# AQE_SENSORMODULE_E2V_CMOS.net
KiCad netlist of a schematic drawn in EAGLE
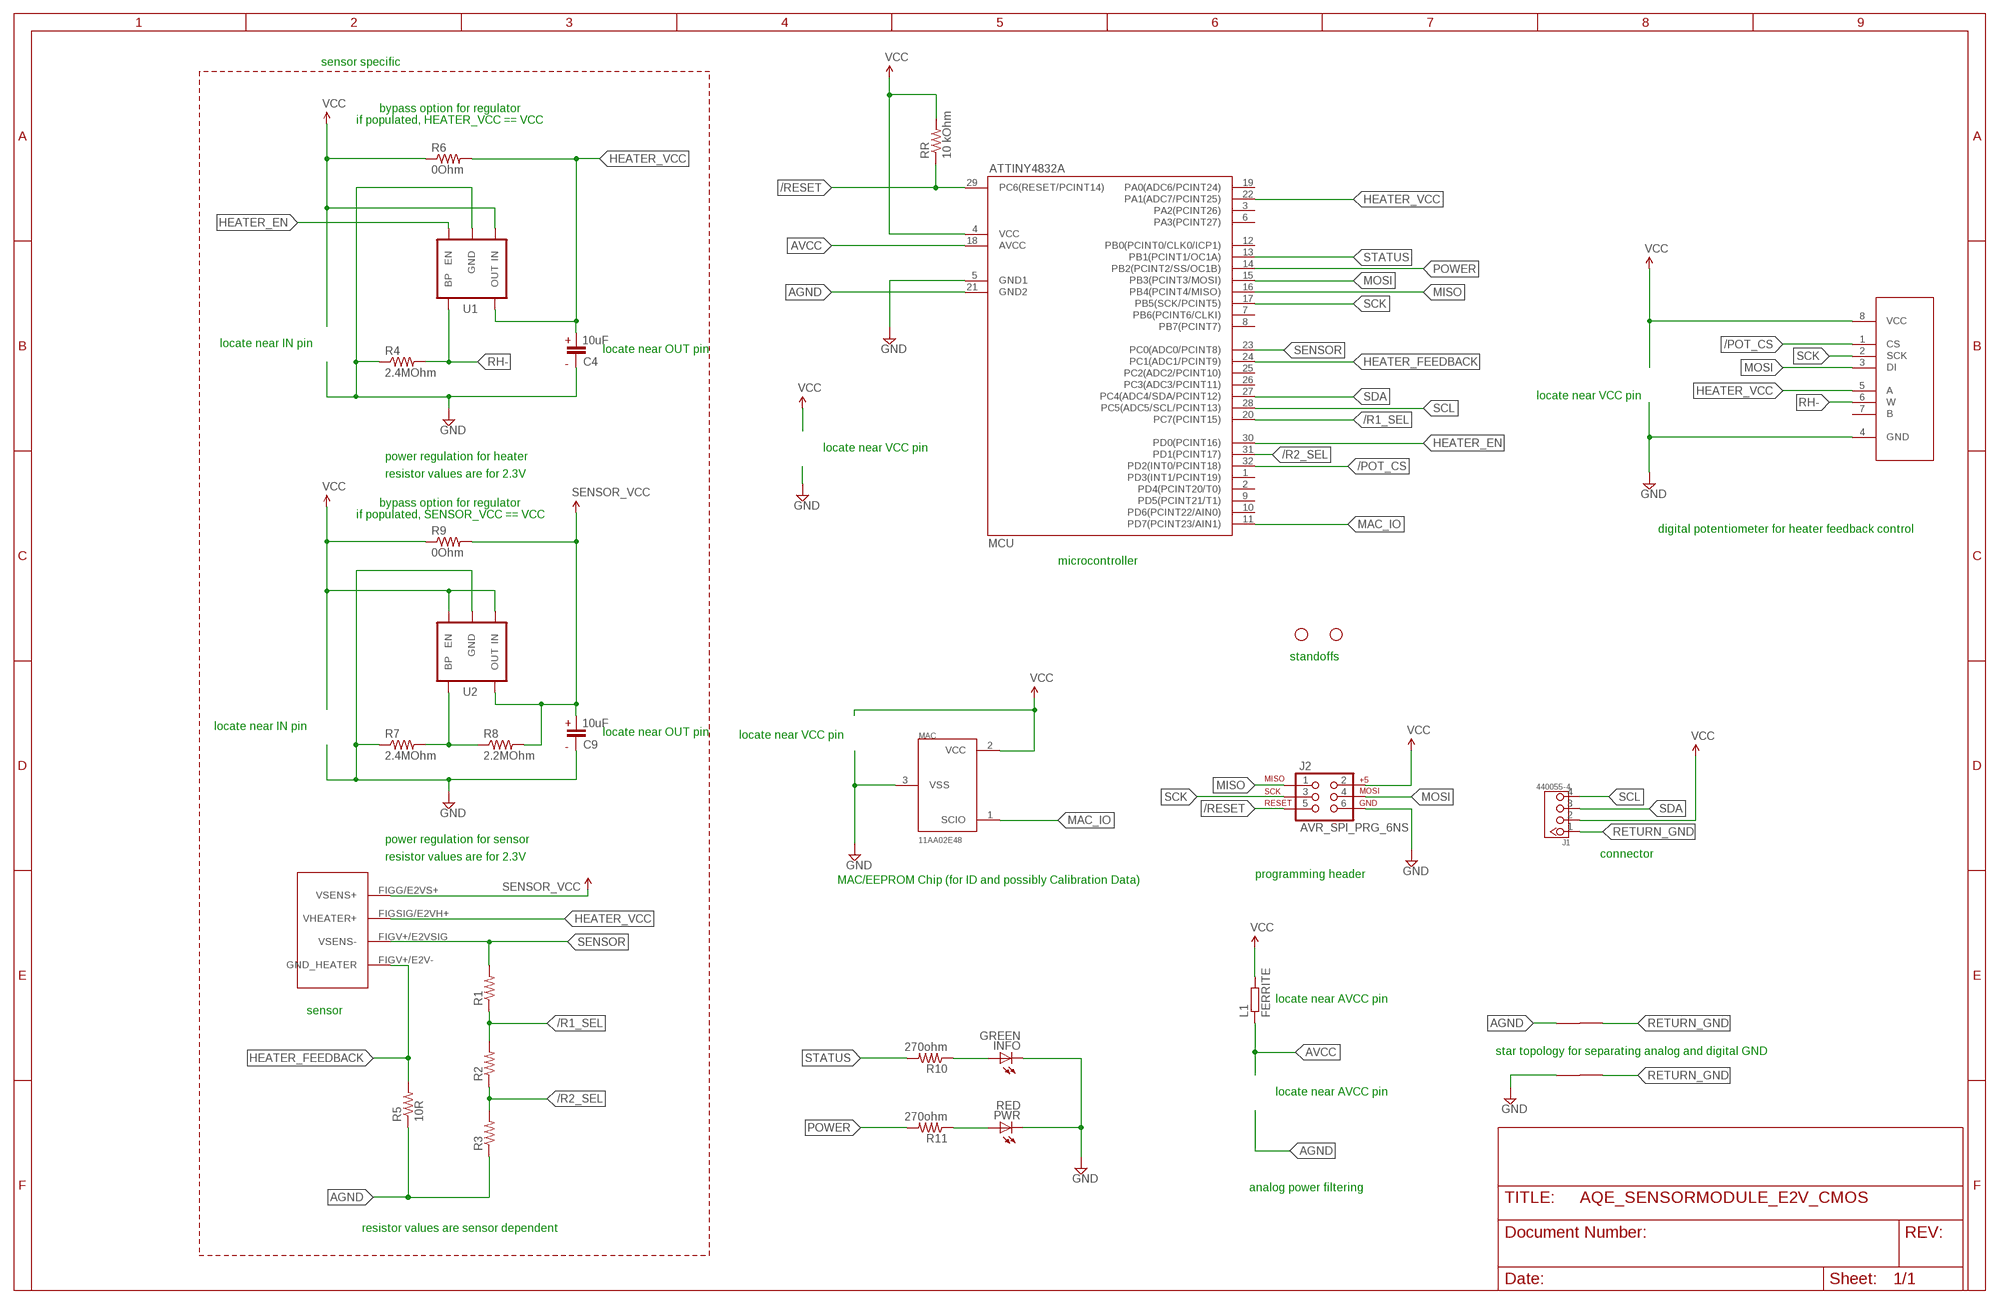
[diagram p0: schematic, sheet 1]

(export (version "E")
  (design (tool "Eeschema 10.0.6"))
  (components
    (comp (ref "C4")
      (value "10uF")
      (footprint "eagle-import:TYPE-B_ALUMINUM_CAN")
      (libsource (lib "eagle-import") (part "EEE-1EA100WR"))
    )
    (comp (ref "C9")
      (value "10uF")
      (footprint "eagle-import:TYPE-B_ALUMINUM_CAN")
      (libsource (lib "eagle-import") (part "EEE-1EA100WR"))
    )
    (comp (ref "GAS")
      (value "E2V")
      (footprint "eagle-import:SR-4")
      (libsource (lib "eagle-import") (part "E2V"))
    )
    (comp (ref "INFO")
      (value "GREEN")
      (footprint "eagle-import:CHIPLED_0805")
      (libsource (lib "eagle-import") (part "LEDCHIPLED_0805"))
    )
    (comp (ref "J1")
      (value "440055-4")
      (footprint "eagle-import:2.0_1X4_90")
      (libsource (lib "eagle-import") (part "TWIG_2.0-DIP-FEMALED"))
    )
    (comp (ref "J2")
      (value "AVR_SPI_PRG_6NS")
      (footprint "eagle-import:2X3-NS")
      (libsource (lib "eagle-import") (part "AVR_SPI_PRG_6NS"))
    )
    (comp (ref "JP1")
      (value "STAND-OFF")
      (footprint "eagle-import:STAND-OFF")
      (libsource (lib "eagle-import") (part "STAND-OFF"))
    )
    (comp (ref "JP2")
      (value "STAND-OFF")
      (footprint "eagle-import:STAND-OFF")
      (libsource (lib "eagle-import") (part "STAND-OFF"))
    )
    (comp (ref "L1")
      (value "FERRITE")
      (footprint "eagle-import:RCL_R0805")
      (libsource (lib "eagle-import") (part "RCL_R-EU_R0805"))
    )
    (comp (ref "MAC")
      (value "11AA02E48")
      (footprint "eagle-import:SOT23")
      (libsource (lib "eagle-import") (part "11AA02E48"))
    )
    (comp (ref "MCU")
      (value "ATTINY4832A")
      (footprint "eagle-import:TQFP32-08")
      (libsource (lib "eagle-import") (part "ATTINY4832A"))
    )
    (comp (ref "PWR")
      (value "RED")
      (footprint "eagle-import:CHIPLED_0805")
      (libsource (lib "eagle-import") (part "LEDCHIPLED_0805"))
    )
    (comp (ref "R1")
      (value "RESISTOR0805-RES")
      (footprint "eagle-import:0805")
      (libsource (lib "eagle-import") (part "RESISTOR0805-RES"))
    )
    (comp (ref "R2")
      (value "RESISTOR0805-RES")
      (footprint "eagle-import:0805")
      (libsource (lib "eagle-import") (part "RESISTOR0805-RES"))
    )
    (comp (ref "R3")
      (value "RESISTOR0805-RES")
      (footprint "eagle-import:0805")
      (libsource (lib "eagle-import") (part "RESISTOR0805-RES"))
    )
    (comp (ref "R4")
      (value "2.4MOhm")
      (footprint "eagle-import:0805")
      (libsource (lib "eagle-import") (part "RESISTOR0805-RES"))
    )
    (comp (ref "R5")
      (value "10R")
      (footprint "eagle-import:0805")
      (libsource (lib "eagle-import") (part "RESISTOR0805-RES"))
    )
    (comp (ref "R6")
      (value "0Ohm")
      (footprint "eagle-import:0805")
      (libsource (lib "eagle-import") (part "RESISTOR0805-RES"))
    )
    (comp (ref "R7")
      (value "2.4MOhm")
      (footprint "eagle-import:0805")
      (libsource (lib "eagle-import") (part "RESISTOR0805-RES"))
    )
    (comp (ref "R8")
      (value "2.2MOhm")
      (footprint "eagle-import:0805")
      (libsource (lib "eagle-import") (part "RESISTOR0805-RES"))
    )
    (comp (ref "R9")
      (value "0Ohm")
      (footprint "eagle-import:0805")
      (libsource (lib "eagle-import") (part "RESISTOR0805-RES"))
    )
    (comp (ref "R10")
      (value "270ohm")
      (footprint "eagle-import:0805")
      (libsource (lib "eagle-import") (part "RESISTOR0805-RES"))
    )
    (comp (ref "R11")
      (value "270ohm")
      (footprint "eagle-import:0805")
      (libsource (lib "eagle-import") (part "RESISTOR0805-RES"))
    )
    (comp (ref "RR")
      (value "10 kOhm")
      (footprint "eagle-import:0805")
      (libsource (lib "eagle-import") (part "RESISTOR0805-RES"))
    )
    (comp (ref "U$2")
      (value "PLANE_COUPLER")
      (footprint "eagle-import:PLANE_COUPLER")
      (libsource (lib "eagle-import") (part "PLANE_COUPLER"))
    )
    (comp (ref "U$3")
      (value "PLANE_COUPLER")
      (footprint "eagle-import:PLANE_COUPLER")
      (libsource (lib "eagle-import") (part "PLANE_COUPLER"))
    )
    (comp (ref "U1")
      (value "V_REG_LDOSMD")
      (footprint "eagle-import:SOT23-5")
      (libsource (lib "eagle-import") (part "V_REG_LDOSMD"))
    )
    (comp (ref "U2")
      (value "V_REG_LDOSMD")
      (footprint "eagle-import:SOT23-5")
      (libsource (lib "eagle-import") (part "V_REG_LDOSMD"))
    )
    (comp (ref "U3")
      (value "MCP41XXX")
      (footprint "eagle-import:SO08")
      (libsource (lib "eagle-import") (part "MCP41XXX"))
    )
  )
  (nets
    (net (code "1") (name "AGND") (class "Default")
      (node (ref "MCU") (pin "21") (pinfunction "GND2_21") (pintype "power_in"))
      (node (ref "R3") (pin "1") (pinfunction "1_1") (pintype "passive"))
      (node (ref "R5") (pin "1") (pinfunction "1_1") (pintype "passive"))
      (node (ref "U$2") (pin "1") (pinfunction "P$1_1") (pintype "bidirectional"))
    )
    (net (code "2") (name "AVCC") (class "Default")
      (node (ref "L1") (pin "1") (pinfunction "1_1") (pintype "passive"))
      (node (ref "MCU") (pin "18") (pinfunction "AVCC_18") (pintype "power_in"))
    )
    (net (code "3") (name "GND") (class "Default")
      (node (ref "C4") (pin "P$2") (pinfunction "2_P$2") (pintype "passive"))
      (node (ref "C9") (pin "P$2") (pinfunction "2_P$2") (pintype "passive"))
      (node (ref "INFO") (pin "C") (pinfunction "C_C") (pintype "passive"))
      (node (ref "J2") (pin "6") (pinfunction "6_6") (pintype "passive"))
      (node (ref "MAC") (pin "3") (pinfunction "VSS_3") (pintype "bidirectional"))
      (node (ref "MCU") (pin "5") (pinfunction "GND1_5") (pintype "power_in"))
      (node (ref "PWR") (pin "C") (pinfunction "C_C") (pintype "passive"))
      (node (ref "R4") (pin "1") (pinfunction "1_1") (pintype "passive"))
      (node (ref "R7") (pin "1") (pinfunction "1_1") (pintype "passive"))
      (node (ref "U$3") (pin "1") (pinfunction "P$1_1") (pintype "bidirectional"))
      (node (ref "U1") (pin "2") (pinfunction "GND_2") (pintype "input"))
      (node (ref "U2") (pin "2") (pinfunction "GND_2") (pintype "input"))
      (node (ref "U3") (pin "4") (pinfunction "GND_4") (pintype "bidirectional"))
    )
    (net (code "4") (name "HEATER_EN") (class "Default")
      (node (ref "MCU") (pin "30") (pinfunction "PD0(PCINT16)_30") (pintype "bidirectional"))
      (node (ref "U1") (pin "3") (pinfunction "EN_3") (pintype "input"))
    )
    (net (code "5") (name "HEATER_FEEDBACK") (class "Default")
      (node (ref "GAS") (pin "FIGV+/E2V-") (pinfunction "GND_HEATER_FIGV+/E2V-") (pintype "bidirectional"))
      (node (ref "MCU") (pin "24") (pinfunction "PC1(ADC1/PCINT9)_24") (pintype "bidirectional"))
      (node (ref "R5") (pin "2") (pinfunction "2_2") (pintype "passive"))
    )
    (net (code "6") (name "HEATER_VCC") (class "Default")
      (node (ref "C4") (pin "P$1") (pinfunction "1_P$1") (pintype "passive"))
      (node (ref "GAS") (pin "FIGSIG/E2VH+") (pinfunction "VHEATER+_FIGSIG/E2VH+") (pintype "bidirectional"))
      (node (ref "MCU") (pin "22") (pinfunction "PA1(ADC7/PCINT25)_22") (pintype "bidirectional"))
      (node (ref "R6") (pin "2") (pinfunction "2_2") (pintype "passive"))
      (node (ref "U1") (pin "5") (pinfunction "OUT_5") (pintype "passive"))
      (node (ref "U3") (pin "5") (pinfunction "A_5") (pintype "bidirectional"))
    )
    (net (code "7") (name "MAC_IO") (class "Default")
      (node (ref "MAC") (pin "1") (pinfunction "SCIO_1") (pintype "bidirectional"))
      (node (ref "MCU") (pin "11") (pinfunction "PD7(PCINT23/AIN1)_11") (pintype "bidirectional"))
    )
    (net (code "8") (name "MISO") (class "Default")
      (node (ref "J2") (pin "1") (pinfunction "1_1") (pintype "passive"))
      (node (ref "MCU") (pin "16") (pinfunction "PB4(PCINT4/MISO)_16") (pintype "bidirectional"))
    )
    (net (code "9") (name "MOSI") (class "Default")
      (node (ref "J2") (pin "4") (pinfunction "4_4") (pintype "passive"))
      (node (ref "MCU") (pin "15") (pinfunction "PB3(PCINT3/MOSI)_15") (pintype "bidirectional"))
      (node (ref "U3") (pin "3") (pinfunction "DI_3") (pintype "bidirectional"))
    )
    (net (code "10") (name "Net-(INFO-PadA)") (class "Default")
      (node (ref "INFO") (pin "A") (pinfunction "A_A") (pintype "passive"))
      (node (ref "R10") (pin "1") (pinfunction "1_1") (pintype "passive"))
    )
    (net (code "11") (name "Net-(PWR-PadA)") (class "Default")
      (node (ref "PWR") (pin "A") (pinfunction "A_A") (pintype "passive"))
      (node (ref "R11") (pin "1") (pinfunction "1_1") (pintype "passive"))
    )
    (net (code "12") (name "Net-(U2-BP)") (class "Default")
      (node (ref "R7") (pin "2") (pinfunction "2_2") (pintype "passive"))
      (node (ref "R8") (pin "1") (pinfunction "1_1") (pintype "passive"))
      (node (ref "U2") (pin "4") (pinfunction "BP_4") (pintype "input"))
    )
    (net (code "13") (name "POWER") (class "Default")
      (node (ref "MCU") (pin "14") (pinfunction "PB2(PCINT2/SS/OC1B)_14") (pintype "bidirectional"))
      (node (ref "R11") (pin "2") (pinfunction "2_2") (pintype "passive"))
    )
    (net (code "14") (name "RETURN_GND") (class "Default")
      (node (ref "J1") (pin "1") (pinfunction "1_1") (pintype "bidirectional"))
      (node (ref "U$2") (pin "2") (pinfunction "P$2_2") (pintype "bidirectional"))
      (node (ref "U$3") (pin "2") (pinfunction "P$2_2") (pintype "bidirectional"))
    )
    (net (code "15") (name "RH-") (class "Default")
      (node (ref "R4") (pin "2") (pinfunction "2_2") (pintype "passive"))
      (node (ref "U1") (pin "4") (pinfunction "BP_4") (pintype "input"))
      (node (ref "U3") (pin "6") (pinfunction "W_6") (pintype "bidirectional"))
    )
    (net (code "16") (name "SCK") (class "Default")
      (node (ref "J2") (pin "3") (pinfunction "3_3") (pintype "passive"))
      (node (ref "MCU") (pin "17") (pinfunction "PB5(SCK/PCINT5)_17") (pintype "bidirectional"))
      (node (ref "U3") (pin "2") (pinfunction "SCK_2") (pintype "bidirectional"))
    )
    (net (code "17") (name "SCL") (class "Default")
      (node (ref "J1") (pin "4") (pinfunction "4_4") (pintype "bidirectional"))
      (node (ref "MCU") (pin "28") (pinfunction "PC5(ADC5/SCL/PCINT13)_28") (pintype "bidirectional"))
    )
    (net (code "18") (name "SDA") (class "Default")
      (node (ref "J1") (pin "3") (pinfunction "3_3") (pintype "bidirectional"))
      (node (ref "MCU") (pin "27") (pinfunction "PC4(ADC4/SDA/PCINT12)_27") (pintype "bidirectional"))
    )
    (net (code "19") (name "SENSOR") (class "Default")
      (node (ref "GAS") (pin "FIGV+/E2VSIG") (pinfunction "VSENS-_FIGV+/E2VSIG") (pintype "bidirectional"))
      (node (ref "MCU") (pin "23") (pinfunction "PC0(ADC0/PCINT8)_23") (pintype "bidirectional"))
      (node (ref "R1") (pin "2") (pinfunction "2_2") (pintype "passive"))
    )
    (net (code "20") (name "SENSOR_VCC") (class "Default")
      (node (ref "C9") (pin "P$1") (pinfunction "1_P$1") (pintype "passive"))
      (node (ref "GAS") (pin "FIGG/E2VS+") (pinfunction "VSENS+_FIGG/E2VS+") (pintype "bidirectional"))
      (node (ref "R8") (pin "2") (pinfunction "2_2") (pintype "passive"))
      (node (ref "R9") (pin "2") (pinfunction "2_2") (pintype "passive"))
      (node (ref "U2") (pin "5") (pinfunction "OUT_5") (pintype "passive"))
    )
    (net (code "21") (name "STATUS") (class "Default")
      (node (ref "MCU") (pin "13") (pinfunction "PB1(PCINT1/OC1A)_13") (pintype "bidirectional"))
      (node (ref "R10") (pin "2") (pinfunction "2_2") (pintype "passive"))
    )
    (net (code "22") (name "VCC") (class "Default")
      (node (ref "J1") (pin "2") (pinfunction "2_2") (pintype "bidirectional"))
      (node (ref "J2") (pin "2") (pinfunction "2_2") (pintype "passive"))
      (node (ref "L1") (pin "2") (pinfunction "2_2") (pintype "passive"))
      (node (ref "MAC") (pin "2") (pinfunction "VCC_2") (pintype "bidirectional"))
      (node (ref "MCU") (pin "4") (pinfunction "VCC_4") (pintype "power_in"))
      (node (ref "R6") (pin "1") (pinfunction "1_1") (pintype "passive"))
      (node (ref "R9") (pin "1") (pinfunction "1_1") (pintype "passive"))
      (node (ref "RR") (pin "2") (pinfunction "2_2") (pintype "passive"))
      (node (ref "U1") (pin "1") (pinfunction "IN_1") (pintype "input"))
      (node (ref "U2") (pin "1") (pinfunction "IN_1") (pintype "input"))
      (node (ref "U2") (pin "3") (pinfunction "EN_3") (pintype "input"))
      (node (ref "U3") (pin "8") (pinfunction "VCC_8") (pintype "bidirectional"))
    )
    (net (code "23") (name "unconnected-(MCU-PA0(ADC6{slash}PCINT24)-Pad19)") (class "Default")
      (node (ref "MCU") (pin "19") (pinfunction "PA0(ADC6/PCINT24)_19") (pintype "bidirectional"))
    )
    (net (code "24") (name "unconnected-(MCU-PA2(PCINT26)-Pad3)") (class "Default")
      (node (ref "MCU") (pin "3") (pinfunction "PA2(PCINT26)_3") (pintype "bidirectional"))
    )
    (net (code "25") (name "unconnected-(MCU-PA3(PCINT27)-Pad6)") (class "Default")
      (node (ref "MCU") (pin "6") (pinfunction "PA3(PCINT27)_6") (pintype "bidirectional"))
    )
    (net (code "26") (name "unconnected-(MCU-PB0(PCINT0{slash}CLK0{slash}ICP1)-Pad12)") (class "Default")
      (node (ref "MCU") (pin "12") (pinfunction "PB0(PCINT0/CLK0/ICP1)_12") (pintype "bidirectional"))
    )
    (net (code "27") (name "unconnected-(MCU-PB6(PCINT6{slash}CLKI)-Pad7)") (class "Default")
      (node (ref "MCU") (pin "7") (pinfunction "PB6(PCINT6/CLKI)_7") (pintype "bidirectional"))
    )
    (net (code "28") (name "unconnected-(MCU-PB7(PCINT7)-Pad8)") (class "Default")
      (node (ref "MCU") (pin "8") (pinfunction "PB7(PCINT7)_8") (pintype "bidirectional"))
    )
    (net (code "29") (name "unconnected-(MCU-PC2(ADC2{slash}PCINT10)-Pad25)") (class "Default")
      (node (ref "MCU") (pin "25") (pinfunction "PC2(ADC2/PCINT10)_25") (pintype "bidirectional"))
    )
    (net (code "30") (name "unconnected-(MCU-PC3(ADC3{slash}PCINT11)-Pad26)") (class "Default")
      (node (ref "MCU") (pin "26") (pinfunction "PC3(ADC3/PCINT11)_26") (pintype "bidirectional"))
    )
    (net (code "31") (name "unconnected-(MCU-PD3(INT1{slash}PCINT19)-Pad1)") (class "Default")
      (node (ref "MCU") (pin "1") (pinfunction "PD3(INT1/PCINT19)_1") (pintype "bidirectional"))
    )
    (net (code "32") (name "unconnected-(MCU-PD4(PCINT20{slash}T0)-Pad2)") (class "Default")
      (node (ref "MCU") (pin "2") (pinfunction "PD4(PCINT20/T0)_2") (pintype "bidirectional"))
    )
    (net (code "33") (name "unconnected-(MCU-PD5(PCINT21{slash}T1)-Pad9)") (class "Default")
      (node (ref "MCU") (pin "9") (pinfunction "PD5(PCINT21/T1)_9") (pintype "bidirectional"))
    )
    (net (code "34") (name "unconnected-(MCU-PD6(PCINT22{slash}AIN0)-Pad10)") (class "Default")
      (node (ref "MCU") (pin "10") (pinfunction "PD6(PCINT22/AIN0)_10") (pintype "bidirectional"))
    )
    (net (code "35") (name "unconnected-(U3-B-Pad7)") (class "Default")
      (node (ref "U3") (pin "7") (pinfunction "B_7") (pintype "bidirectional"))
    )
    (net (code "36") (name "{slash}POT_CS") (class "Default")
      (node (ref "MCU") (pin "32") (pinfunction "PD2(INT0/PCINT18)_32") (pintype "bidirectional"))
      (node (ref "U3") (pin "1") (pinfunction "CS_1") (pintype "bidirectional"))
    )
    (net (code "37") (name "{slash}R1_SEL") (class "Default")
      (node (ref "MCU") (pin "20") (pinfunction "PC7(PCINT15)_20") (pintype "bidirectional"))
      (node (ref "R1") (pin "1") (pinfunction "1_1") (pintype "passive"))
      (node (ref "R2") (pin "2") (pinfunction "2_2") (pintype "passive"))
    )
    (net (code "38") (name "{slash}R2_SEL") (class "Default")
      (node (ref "MCU") (pin "31") (pinfunction "PD1(PCINT17)_31") (pintype "bidirectional"))
      (node (ref "R2") (pin "1") (pinfunction "1_1") (pintype "passive"))
      (node (ref "R3") (pin "2") (pinfunction "2_2") (pintype "passive"))
    )
    (net (code "39") (name "{slash}RESET") (class "Default")
      (node (ref "J2") (pin "5") (pinfunction "5_5") (pintype "passive"))
      (node (ref "MCU") (pin "29") (pinfunction "PC6(RESET/PCINT14)_29") (pintype "bidirectional"))
      (node (ref "RR") (pin "1") (pinfunction "1_1") (pintype "passive"))
    )
  )
)
